# ATTINY85-V3_1.net
KiCad netlist of a schematic drawn in EAGLE
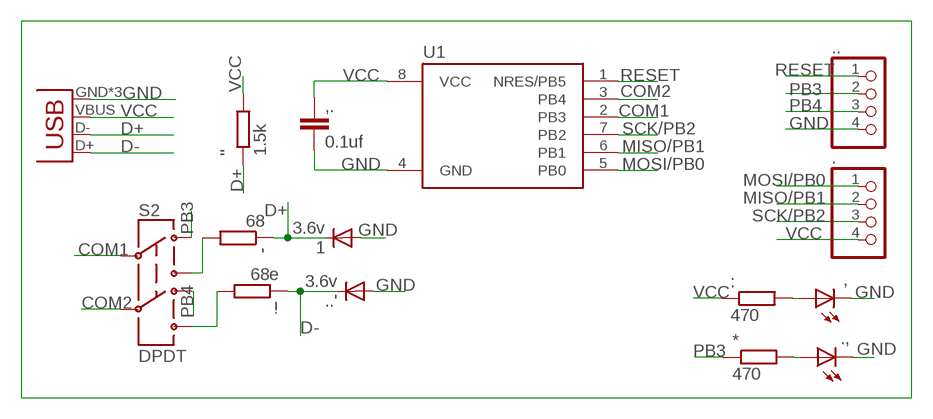
[diagram p0: schematic, sheet 1]

(export (version "E")
  (design (tool "Eeschema 10.0.6"))
  (components
    (comp (ref "!")
      (value "68e")
      (footprint "eagle-import:M0805")
      (libsource (lib "eagle-import") (part "R-EU_M0805"))
    )
    (comp (ref "'")
      (value "68")
      (footprint "eagle-import:M0805")
      (libsource (lib "eagle-import") (part "R-EU_M0805"))
    )
    (comp (ref "''")
      (value "1.5k")
      (footprint "eagle-import:M0805")
      (libsource (lib "eagle-import") (part "R-EU_M0805"))
    )
    (comp (ref "*")
      (value "470")
      (footprint "eagle-import:M0805")
      (libsource (lib "eagle-import") (part "R-EU_M0805"))
    )
    (comp (ref "+")
      (value "USB-MICROB")
      (footprint "eagle-import:USB-MICROB")
      (libsource (lib "eagle-import") (part "USB-MICROB"))
    )
    (comp (ref ",")
      (value "LEDSML0805")
      (footprint "eagle-import:SML0805")
      (libsource (lib "eagle-import") (part "LEDSML0805"))
    )
    (comp (ref ",.")
      (value "0.1uf")
      (footprint "eagle-import:C0805K")
      (libsource (lib "eagle-import") (part "C-EUC0805K"))
    )
    (comp (ref ".")
      (value "HEADER-1X4ROUND")
      (footprint "eagle-import:1X04_ROUND")
      (libsource (lib "eagle-import") (part "HEADER-1X4ROUND"))
    )
    (comp (ref ".,")
      (value "LEDSML0805")
      (footprint "eagle-import:SML0805")
      (libsource (lib "eagle-import") (part "LEDSML0805"))
    )
    (comp (ref "..")
      (value "HEADER-1X4ROUND")
      (footprint "eagle-import:1X04_ROUND")
      (libsource (lib "eagle-import") (part "HEADER-1X4ROUND"))
    )
    (comp (ref "..'")
      (value "3.6v")
      (footprint "eagle-import:MINIMELF")
      (libsource (lib "eagle-import") (part "DIODE-MINIMELF"))
    )
    (comp (ref "1")
      (value "3.6v")
      (footprint "eagle-import:MINIMELF")
      (libsource (lib "eagle-import") (part "DIODE-MINIMELF"))
    )
    (comp (ref ":")
      (value "470")
      (footprint "eagle-import:M0805")
      (libsource (lib "eagle-import") (part "R-EU_M0805"))
    )
    (comp (ref "S2")
      (value "DPDT")
      (footprint "eagle-import:AYZ0202")
      (libsource (lib "eagle-import") (part "SWITCH-DPDTAYZ0202"))
    )
    (comp (ref "U1")
      (value "ATTINY85-20S")
      (footprint "eagle-import:SOIC8_EIAJ_208MIL")
      (libsource (lib "eagle-import") (part "ATTINY85S-20"))
    )
  )
  (nets
    (net (code "1") (name "/COM1") (class "Default")
      (node (ref "S2") (pin "2") (pinfunction "2_2") (pintype "bidirectional"))
      (node (ref "U1") (pin "2") (pinfunction "PB3_2") (pintype "bidirectional"))
    )
    (net (code "2") (name "/COM2") (class "Default")
      (node (ref "S2") (pin "5") (pinfunction "5_5") (pintype "bidirectional"))
      (node (ref "U1") (pin "3") (pinfunction "PB4_3") (pintype "bidirectional"))
    )
    (net (code "3") (name "/D+") (class "Default")
      (node (ref "'") (pin "1") (pinfunction "1_1") (pintype "passive"))
      (node (ref "''") (pin "1") (pinfunction "1_1") (pintype "passive"))
      (node (ref "+") (pin "D-") (pinfunction "D-_D-") (pintype "bidirectional"))
      (node (ref "1") (pin "C") (pinfunction "C_C") (pintype "passive"))
    )
    (net (code "4") (name "/D-") (class "Default")
      (node (ref "!") (pin "1") (pinfunction "1_1") (pintype "passive"))
      (node (ref "+") (pin "D+") (pinfunction "D+_D+") (pintype "bidirectional"))
      (node (ref "..'") (pin "C") (pinfunction "C_C") (pintype "passive"))
    )
    (net (code "5") (name "/GND") (class "Default")
      (node (ref "+") (pin "GND") (pinfunction "GND_GND") (pintype "bidirectional"))
      (node (ref "+") (pin "MT1") (pinfunction "GND_MT1") (pintype "bidirectional"))
      (node (ref "+") (pin "MT2") (pinfunction "GND_MT2") (pintype "bidirectional"))
      (node (ref ",") (pin "C") (pinfunction "C_C") (pintype "passive"))
      (node (ref ",.") (pin "2") (pinfunction "2_2") (pintype "passive"))
      (node (ref ".,") (pin "C") (pinfunction "C_C") (pintype "passive"))
      (node (ref "..") (pin "4") (pinfunction "4_4") (pintype "passive"))
      (node (ref "..'") (pin "A") (pinfunction "A_A") (pintype "passive"))
      (node (ref "1") (pin "A") (pinfunction "A_A") (pintype "passive"))
      (node (ref "U1") (pin "4") (pinfunction "GND_4") (pintype "power_in"))
    )
    (net (code "6") (name "/MISO{slash}PB1") (class "Default")
      (node (ref ".") (pin "2") (pinfunction "2_2") (pintype "passive"))
      (node (ref "U1") (pin "6") (pinfunction "PB1_6") (pintype "bidirectional"))
    )
    (net (code "7") (name "/MOSI{slash}PB0") (class "Default")
      (node (ref ".") (pin "1") (pinfunction "1_1") (pintype "passive"))
      (node (ref "U1") (pin "5") (pinfunction "PB0_5") (pintype "bidirectional"))
    )
    (net (code "8") (name "/PB3") (class "Default")
      (node (ref "*") (pin "1") (pinfunction "1_1") (pintype "passive"))
      (node (ref "..") (pin "2") (pinfunction "2_2") (pintype "passive"))
      (node (ref "S2") (pin "1") (pinfunction "1_1") (pintype "bidirectional"))
    )
    (net (code "9") (name "/PB4") (class "Default")
      (node (ref "..") (pin "3") (pinfunction "3_3") (pintype "passive"))
      (node (ref "S2") (pin "4") (pinfunction "4_4") (pintype "bidirectional"))
    )
    (net (code "10") (name "/RESET") (class "Default")
      (node (ref "..") (pin "1") (pinfunction "1_1") (pintype "passive"))
      (node (ref "U1") (pin "1") (pinfunction "NRES/PB5_1") (pintype "bidirectional"))
    )
    (net (code "11") (name "/SCK{slash}PB2") (class "Default")
      (node (ref ".") (pin "3") (pinfunction "3_3") (pintype "passive"))
      (node (ref "U1") (pin "7") (pinfunction "PB2_7") (pintype "bidirectional"))
    )
    (net (code "12") (name "/VCC") (class "Default")
      (node (ref "''") (pin "2") (pinfunction "2_2") (pintype "passive"))
      (node (ref "+") (pin "VBUS") (pinfunction "VBUS_VBUS") (pintype "bidirectional"))
      (node (ref ",.") (pin "1") (pinfunction "1_1") (pintype "passive"))
      (node (ref ".") (pin "4") (pinfunction "4_4") (pintype "passive"))
      (node (ref ":") (pin "1") (pinfunction "1_1") (pintype "passive"))
      (node (ref "U1") (pin "8") (pinfunction "VCC_8") (pintype "power_in"))
    )
    (net (code "13") (name "Net-(!-Pad2)") (class "Default")
      (node (ref "!") (pin "2") (pinfunction "2_2") (pintype "passive"))
      (node (ref "S2") (pin "6") (pinfunction "6_6") (pintype "bidirectional"))
    )
    (net (code "14") (name "Net-('-Pad2)") (class "Default")
      (node (ref "'") (pin "2") (pinfunction "2_2") (pintype "passive"))
      (node (ref "S2") (pin "3") (pinfunction "3_3") (pintype "bidirectional"))
    )
    (net (code "15") (name "Net-(*-Pad2)") (class "Default")
      (node (ref "*") (pin "2") (pinfunction "2_2") (pintype "passive"))
      (node (ref ".,") (pin "A") (pinfunction "A_A") (pintype "passive"))
    )
    (net (code "16") (name "Net-(,-PadA)") (class "Default")
      (node (ref ",") (pin "A") (pinfunction "A_A") (pintype "passive"))
      (node (ref ":") (pin "2") (pinfunction "2_2") (pintype "passive"))
    )
  )
)
